# EVENTCTRL_TOP.net
KiCad netlist of a schematic drawn in Altium Designer
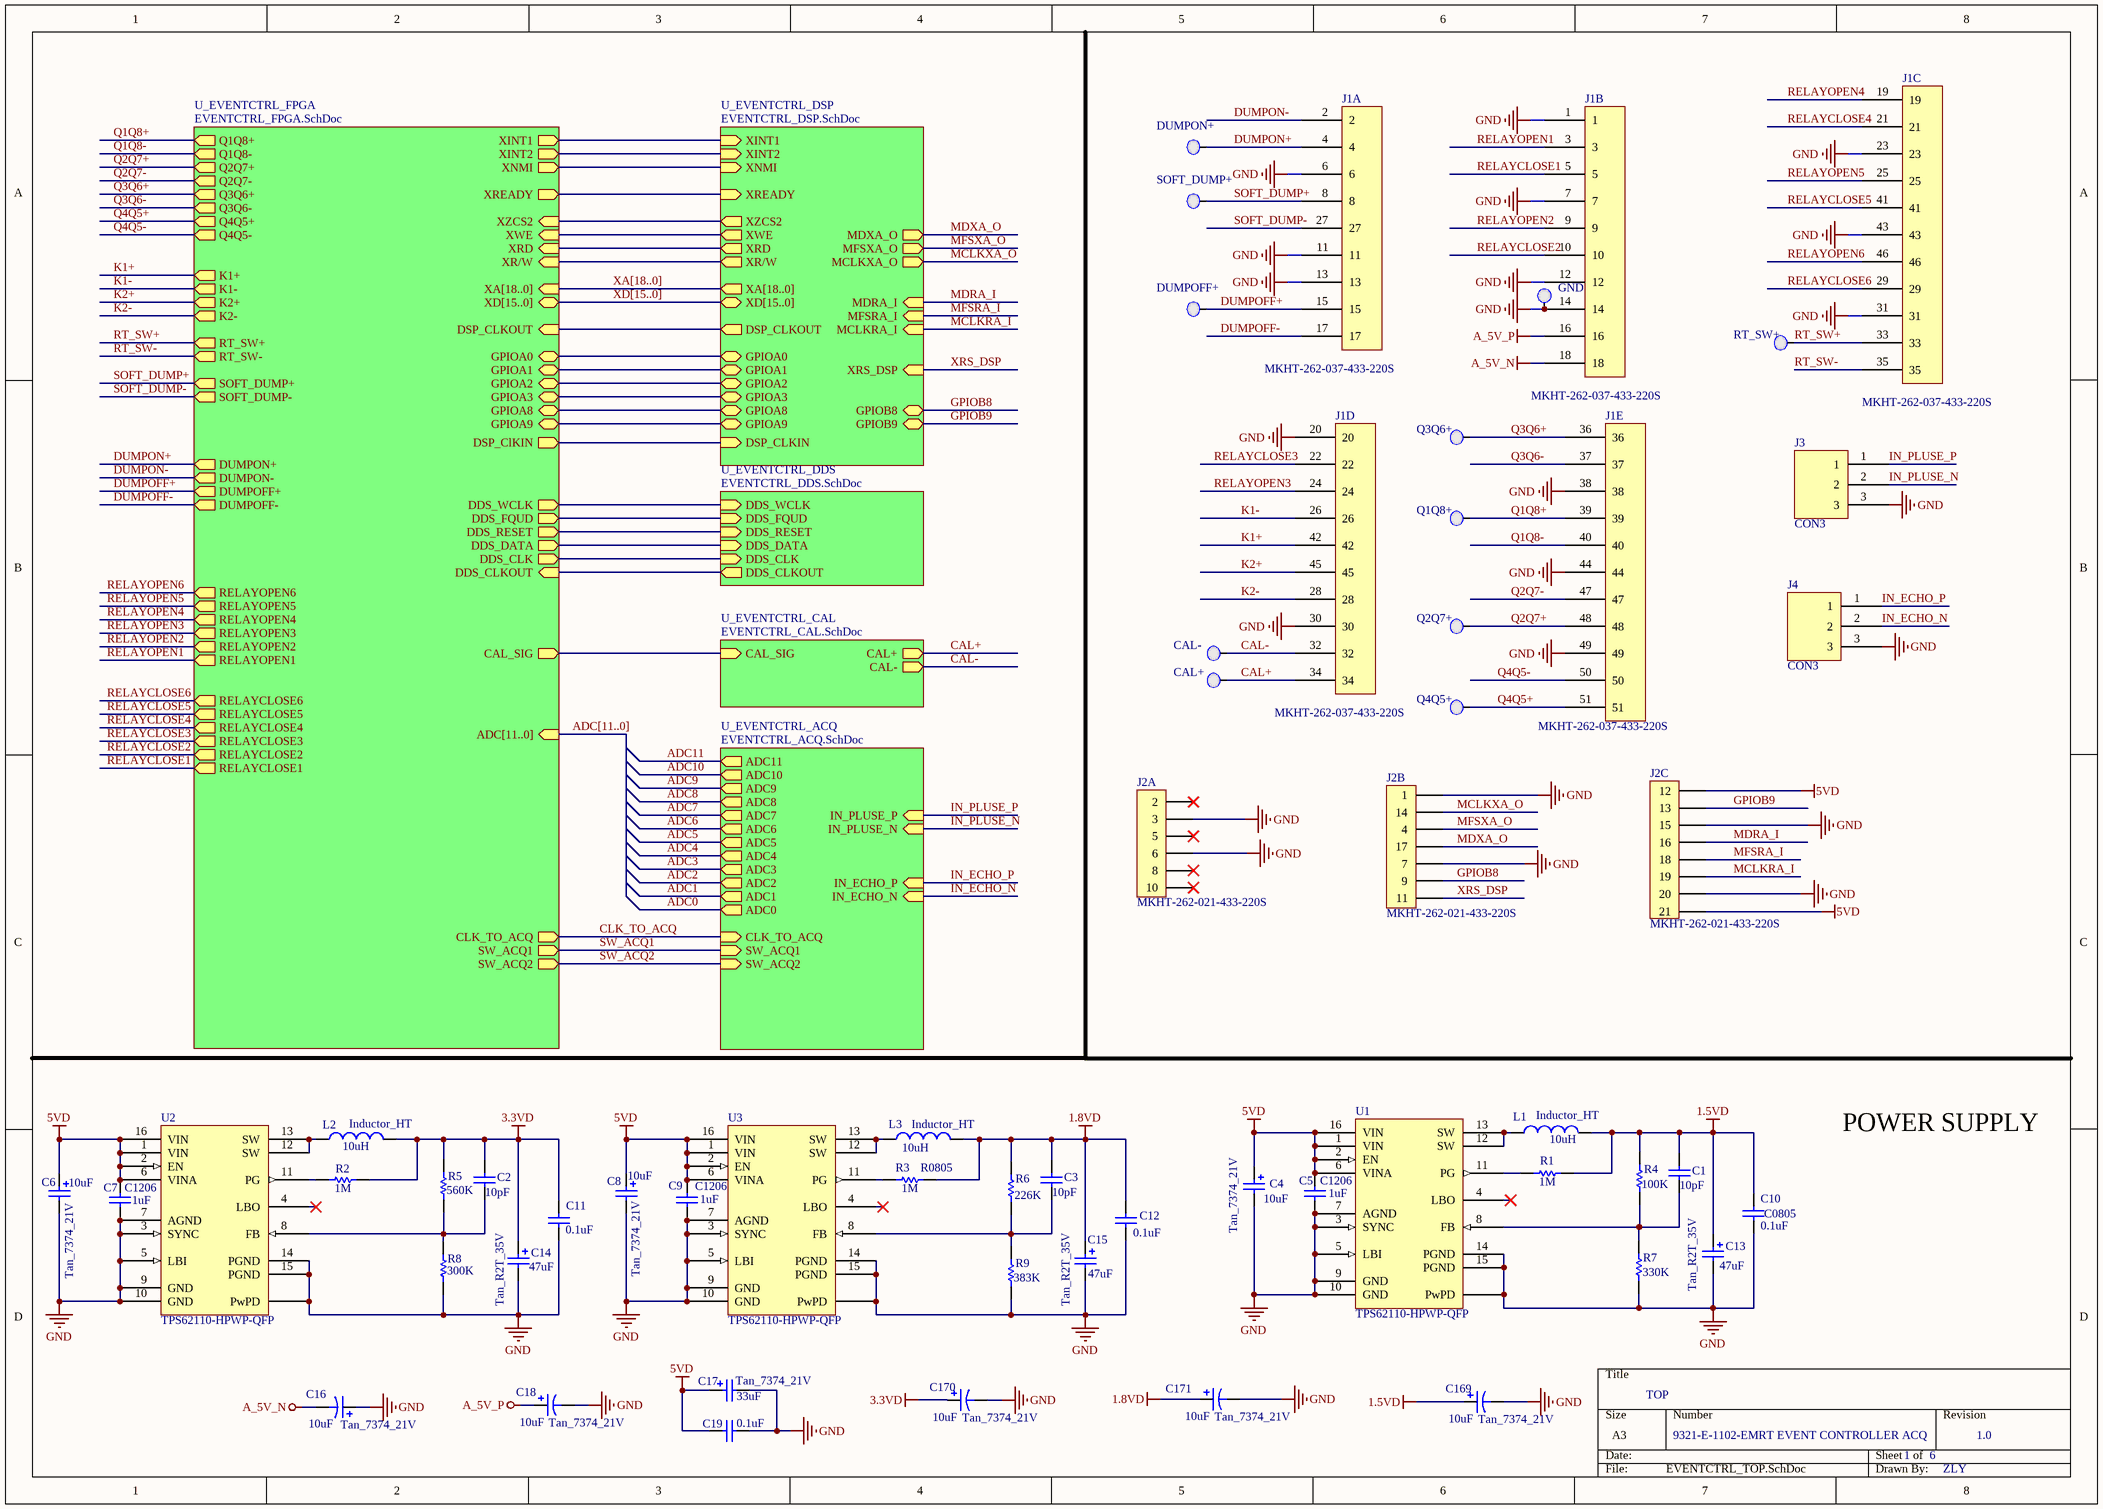
[diagram p0: EVENTCTRL_TOP.SchDoc]

(export (version "E")
  (design (tool "Eeschema 10.0.6"))
  (components
    (comp (ref "C1")
      (value "10pF")
      (footprint "0805")
      (description "Capacitor")
      (fields (field (name "PART NUMBER") "Y20025162") (field (name "Comment") "C0805"))
      (libsource (lib "Cap") (part "Cap"))
    )
    (comp (ref "C2")
      (value "10pF")
      (footprint "0805")
      (description "Capacitor")
      (fields (field (name "PART NUMBER") "Y20025162") (field (name "Comment") "C0805"))
      (libsource (lib "Cap") (part "Cap"))
    )
    (comp (ref "C3")
      (value "10pF")
      (footprint "0805")
      (description "Capacitor")
      (fields (field (name "PART NUMBER") "Y20025162") (field (name "Comment") "C0805"))
      (libsource (lib "Cap") (part "Cap"))
    )
    (comp (ref "C4")
      (value "Tan_7374_21V")
      (footprint "7343")
      (description "Polarized Capacitor")
      (fields (field (name "ALTIUM_VALUE") "10uF") (field (name "PART NUMBER") "Y20024815"))
      (libsource (lib "Cap Pol") (part "Cap Pol"))
    )
    (comp (ref "C5")
      (value "C1206")
      (footprint "1206")
      (description "Capacitor")
      (fields (field (name "ALTIUM_VALUE") "1uF") (field (name "PART NUMBER") "Y20024113"))
      (libsource (lib "Cap") (part "Cap"))
    )
    (comp (ref "C6")
      (value "Tan_7374_21V")
      (footprint "7343")
      (description "Polarized Capacitor")
      (fields (field (name "ALTIUM_VALUE") "10uF") (field (name "PART NUMBER") "Y20024815"))
      (libsource (lib "Cap Pol") (part "Cap Pol"))
    )
    (comp (ref "C7")
      (value "C1206")
      (footprint "1206")
      (description "Capacitor")
      (fields (field (name "ALTIUM_VALUE") "1uF") (field (name "PART NUMBER") "Y20024113"))
      (libsource (lib "Cap") (part "Cap"))
    )
    (comp (ref "C8")
      (value "Tan_7374_21V")
      (footprint "7343")
      (description "Polarized Capacitor")
      (fields (field (name "ALTIUM_VALUE") "10uF") (field (name "PART NUMBER") "Y20024815"))
      (libsource (lib "Cap Pol") (part "Cap Pol"))
    )
    (comp (ref "C9")
      (value "C1206")
      (footprint "1206")
      (description "Capacitor")
      (fields (field (name "ALTIUM_VALUE") "1uF") (field (name "PART NUMBER") "Y20024113"))
      (libsource (lib "Cap") (part "Cap"))
    )
    (comp (ref "C10")
      (value "C0805")
      (footprint "0805")
      (description "Capacitor")
      (fields (field (name "ALTIUM_VALUE") "0.1uF") (field (name "PART NUMBER") "Y20025084"))
      (libsource (lib "Cap") (part "Cap"))
    )
    (comp (ref "C11")
      (value "0.1uF")
      (footprint "0805")
      (description "Capacitor")
      (fields (field (name "PART NUMBER") "Y20025084") (field (name "Comment") "C0805"))
      (libsource (lib "Cap") (part "Cap"))
    )
    (comp (ref "C12")
      (value "0.1uF")
      (footprint "0805")
      (description "Capacitor")
      (fields (field (name "PART NUMBER") "Y20025084") (field (name "Comment") "C0805"))
      (libsource (lib "Cap") (part "Cap"))
    )
    (comp (ref "C13")
      (value "Tan_R2T_35V")
      (footprint "7343")
      (description "Polarized Capacitor")
      (fields (field (name "ALTIUM_VALUE") "47uF") (field (name "PART NUMBER") "Y20024816"))
      (libsource (lib "Cap Pol") (part "Cap Pol"))
    )
    (comp (ref "C14")
      (value "Tan_R2T_35V")
      (footprint "7343")
      (description "Polarized Capacitor")
      (fields (field (name "ALTIUM_VALUE") "47uF") (field (name "PART NUMBER") "Y20024816"))
      (libsource (lib "Cap Pol") (part "Cap Pol"))
    )
    (comp (ref "C15")
      (value "Tan_R2T_35V")
      (footprint "7343")
      (description "Polarized Capacitor")
      (fields (field (name "ALTIUM_VALUE") "47uF") (field (name "PART NUMBER") "Y20024816"))
      (libsource (lib "Cap Pol") (part "Cap Pol"))
    )
    (comp (ref "C16")
      (value "Tan_7374_21V")
      (footprint "7343")
      (description "Polarized Capacitor (Radial)")
      (fields (field (name "ALTIUM_VALUE") "10uF"))
      (libsource (lib "Miscellaneous Devices") (part "Cap Pol1"))
    )
    (comp (ref "C17")
      (value "Tan_7374_21V")
      (footprint "7343")
      (description "Polarized Capacitor")
      (fields (field (name "ALTIUM_VALUE") "33uF") (field (name "PART NUMBER") "Y20028884"))
      (libsource (lib "Cap Pol") (part "Cap Pol"))
    )
    (comp (ref "C18")
      (value "Tan_7374_21V")
      (footprint "7343")
      (description "Polarized Capacitor (Radial)")
      (fields (field (name "ALTIUM_VALUE") "10uF"))
      (libsource (lib "Miscellaneous Devices") (part "Cap Pol1"))
    )
    (comp (ref "C19")
      (value "0.1uF")
      (footprint "0805")
      (description "Capacitor")
      (fields (field (name "PART NUMBER") "Y20025084") (field (name "Comment") "C0805"))
      (libsource (lib "Cap") (part "Cap"))
    )
    (comp (ref "C169")
      (value "Tan_7374_21V")
      (footprint "7343")
      (description "Polarized Capacitor (Radial)")
      (fields (field (name "ALTIUM_VALUE") "10uF"))
      (libsource (lib "Miscellaneous Devices") (part "Cap Pol1"))
    )
    (comp (ref "C170")
      (value "Tan_7374_21V")
      (footprint "7343")
      (description "Polarized Capacitor (Radial)")
      (fields (field (name "ALTIUM_VALUE") "10uF"))
      (libsource (lib "Miscellaneous Devices") (part "Cap Pol1"))
    )
    (comp (ref "C171")
      (value "Tan_7374_21V")
      (footprint "7343")
      (description "Polarized Capacitor (Radial)")
      (fields (field (name "ALTIUM_VALUE") "10uF"))
      (libsource (lib "Miscellaneous Devices") (part "Cap Pol1"))
    )
    (comp (ref "CAL+") (value "TP") (footprint "TPA") (libsource (lib "*") (part "TP")))
    (comp (ref "CAL-") (value "TP") (footprint "TPA") (libsource (lib "*") (part "TP")))
    (comp (ref "DUMPOFF+") (value "TP") (footprint "TPA") (libsource (lib "*") (part "TP")))
    (comp (ref "DUMPON+") (value "TP") (footprint "TPA") (libsource (lib "*") (part "TP")))
    (comp (ref "GND") (value "TP") (footprint "TPA") (libsource (lib "") (part "TP_1")))
    (comp (ref "J1")
      (value "MKHT-262-037-433-220S")
      (footprint "MKHT-262-037-433-220S-51")
      (libsource (lib "ENEVT_SIP_MCM") (part "MKHT-262-037-433-220S"))
    )
    (comp (ref "J2")
      (value "MKHT-262-021-433-220S")
      (footprint "AIRBORN_21")
      (libsource (lib "srj") (part "MKHT-262-021-433-220S"))
    )
    (comp (ref "J3") (value "CON3") (footprint "HEAT3") (libsource (lib "srj") (part "CON3")))
    (comp (ref "J4") (value "CON3") (footprint "HEAT3") (libsource (lib "srj") (part "CON3")))
    (comp (ref "L1")
      (value "Inductor_HT")
      (footprint "Inductor_HT")
      (description "Inductor-1")
      (fields (field (name "PART NUMBER") "Y20028214") (field (name "ALTIUM_VALUE") "10uH"))
      (libsource (lib "B82422H1103K000") (part "B82422H1103K000"))
    )
    (comp (ref "L2")
      (value "Inductor_HT")
      (footprint "Inductor_HT")
      (description "Inductor-1")
      (fields (field (name "PART NUMBER") "Y20028214") (field (name "ALTIUM_VALUE") "10uH"))
      (libsource (lib "B82422H1103K000") (part "B82422H1103K000"))
    )
    (comp (ref "L3")
      (value "Inductor_HT")
      (footprint "Inductor_HT")
      (description "Inductor-1")
      (fields (field (name "PART NUMBER") "Y20028214") (field (name "ALTIUM_VALUE") "10uH"))
      (libsource (lib "B82422H1103K000") (part "B82422H1103K000"))
    )
    (comp (ref "Q1Q8+") (value "TP") (footprint "TPA") (libsource (lib "*") (part "TP")))
    (comp (ref "Q2Q7+") (value "TP") (footprint "TPA") (libsource (lib "*") (part "TP")))
    (comp (ref "Q3Q6+") (value "TP") (footprint "TPA") (libsource (lib "*") (part "TP")))
    (comp (ref "Q4Q5+") (value "TP") (footprint "TPA") (libsource (lib "*") (part "TP")))
    (comp (ref "R1")
      (value "1M")
      (footprint "R0805")
      (description "Resistor")
      (fields (field (name "Comment") "R0805") (field (name "PUBLISHER") "Altium Limited"))
      (libsource (lib "Miscellaneous Devices") (part "Res1"))
    )
    (comp (ref "R2")
      (value "1M")
      (footprint "R0805")
      (description "Resistor")
      (fields (field (name "Comment") "R0805") (field (name "PUBLISHER") "Altium Limited"))
      (libsource (lib "Miscellaneous Devices") (part "Res1"))
    )
    (comp (ref "R3")
      (value "R0805")
      (footprint "R0805")
      (description "Resistor")
      (fields (field (name "ALTIUM_VALUE") "1M") (field (name "PUBLISHER") "Altium Limited"))
      (libsource (lib "Miscellaneous Devices") (part "Res1"))
    )
    (comp (ref "R4")
      (value "100K")
      (footprint "R0805")
      (description "Resistor")
      (fields (field (name "Comment") "R0805") (field (name "PUBLISHER") "Altium Limited"))
      (libsource (lib "Miscellaneous Devices") (part "Res1"))
    )
    (comp (ref "R5")
      (value "560K")
      (footprint "R0805")
      (description "Resistor")
      (fields (field (name "Comment") "R0805") (field (name "PUBLISHER") "Altium Limited"))
      (libsource (lib "Miscellaneous Devices") (part "Res1"))
    )
    (comp (ref "R6")
      (value "226K")
      (footprint "R0805")
      (description "Resistor")
      (fields (field (name "Comment") "R0805") (field (name "PUBLISHER") "Altium Limited"))
      (libsource (lib "Miscellaneous Devices") (part "Res1"))
    )
    (comp (ref "R7")
      (value "330K")
      (footprint "R0805")
      (description "Resistor")
      (fields (field (name "Comment") "R0805") (field (name "PUBLISHER") "Altium Limited"))
      (libsource (lib "Miscellaneous Devices") (part "Res1"))
    )
    (comp (ref "R8")
      (value "300K")
      (footprint "R0805")
      (description "Resistor")
      (fields (field (name "Comment") "R0805") (field (name "PUBLISHER") "Altium Limited"))
      (libsource (lib "Miscellaneous Devices") (part "Res1"))
    )
    (comp (ref "R9")
      (value "383K")
      (footprint "R0805")
      (description "Resistor")
      (fields (field (name "Comment") "R0805") (field (name "PUBLISHER") "Altium Limited"))
      (libsource (lib "Miscellaneous Devices") (part "Res1"))
    )
    (comp (ref "RT_SW+") (value "TP") (footprint "TPA") (libsource (lib "*") (part "TP")))
    (comp (ref "SOFT_DUMP+") (value "TP") (footprint "TPA") (libsource (lib "*") (part "TP")))
    (comp (ref "U1")
      (value "TPS62110-HPWP-QFP")
      (footprint "PWP16")
      (fields (field (name "PART NUMBER") "Y20033002"))
      (libsource (lib "TPS62110-HT") (part "TPS62110-HPWP"))
    )
    (comp (ref "U2")
      (value "TPS62110-HPWP-QFP")
      (footprint "PWP16")
      (fields (field (name "PART NUMBER") "Y20033002"))
      (libsource (lib "TPS62110-HT") (part "TPS62110-HPWP"))
    )
    (comp (ref "U3")
      (value "TPS62110-HPWP-QFP")
      (footprint "PWP16")
      (fields (field (name "PART NUMBER") "Y20033002"))
      (libsource (lib "TPS62110-HT") (part "TPS62110-HPWP"))
    )
  )
  (nets
    (net (code "49") (name "/CAL+") (class "Default")
      (node (ref "CAL+") (pin "1") (pinfunction "TP_1") (pintype "passive"))
      (node (ref "J1") (pin "34") (pinfunction "34_34") (pintype "passive"))
    )
    (net (code "50") (name "/CAL-") (class "Default")
      (node (ref "CAL-") (pin "1") (pinfunction "TP_1") (pintype "passive"))
      (node (ref "J1") (pin "32") (pinfunction "32_32") (pintype "passive"))
    )
    (net (code "61") (name "/DUMPOFF+") (class "Default")
      (node (ref "DUMPOFF+") (pin "1") (pinfunction "TP_1") (pintype "passive"))
      (node (ref "J1") (pin "15") (pinfunction "15_15") (pintype "passive"))
    )
    (net (code "62") (name "/DUMPOFF-") (class "Default")
      (node (ref "J1") (pin "17") (pinfunction "17_17") (pintype "passive"))
    )
    (net (code "63") (name "/DUMPON+") (class "Default")
      (node (ref "DUMPON+") (pin "1") (pinfunction "TP_1") (pintype "passive"))
      (node (ref "J1") (pin "4") (pinfunction "4_4") (pintype "passive"))
    )
    (net (code "64") (name "/DUMPON-") (class "Default")
      (node (ref "J1") (pin "2") (pinfunction "2_2") (pintype "passive"))
    )
    (net (code "71") (name "/GPIOB8") (class "Default")
      (node (ref "J2") (pin "9") (pinfunction "9_9") (pintype "passive"))
    )
    (net (code "72") (name "/GPIOB9") (class "Default")
      (node (ref "J2") (pin "13") (pinfunction "13_13") (pintype "passive"))
    )
    (net (code "73") (name "/IN_ECHO_N") (class "Default")
      (node (ref "J4") (pin "2") (pinfunction "2_2") (pintype "passive"))
    )
    (net (code "74") (name "/IN_ECHO_P") (class "Default")
      (node (ref "J4") (pin "1") (pinfunction "1_1") (pintype "passive"))
    )
    (net (code "75") (name "/IN_PLUSE_N") (class "Default")
      (node (ref "J3") (pin "2") (pinfunction "2_2") (pintype "passive"))
    )
    (net (code "76") (name "/IN_PLUSE_P") (class "Default")
      (node (ref "J3") (pin "1") (pinfunction "1_1") (pintype "passive"))
    )
    (net (code "77") (name "/K1+") (class "Default")
      (node (ref "J1") (pin "42") (pinfunction "42_42") (pintype "passive"))
    )
    (net (code "78") (name "/K1-") (class "Default")
      (node (ref "J1") (pin "26") (pinfunction "26_26") (pintype "passive"))
    )
    (net (code "79") (name "/K2+") (class "Default")
      (node (ref "J1") (pin "45") (pinfunction "45_45") (pintype "passive"))
    )
    (net (code "80") (name "/K2-") (class "Default")
      (node (ref "J1") (pin "28") (pinfunction "28_28") (pintype "passive"))
    )
    (net (code "81") (name "/MCLKRA_I") (class "Default")
      (node (ref "J2") (pin "19") (pinfunction "19_19") (pintype "passive"))
    )
    (net (code "82") (name "/MCLKXA_O") (class "Default")
      (node (ref "J2") (pin "14") (pinfunction "14_14") (pintype "passive"))
    )
    (net (code "83") (name "/MDRA_I") (class "Default")
      (node (ref "J2") (pin "16") (pinfunction "16_16") (pintype "passive"))
    )
    (net (code "84") (name "/MDXA_O") (class "Default")
      (node (ref "J2") (pin "17") (pinfunction "17_17") (pintype "passive"))
    )
    (net (code "85") (name "/MFSRA_I") (class "Default")
      (node (ref "J2") (pin "18") (pinfunction "18_18") (pintype "passive"))
    )
    (net (code "86") (name "/MFSXA_O") (class "Default")
      (node (ref "J2") (pin "4") (pinfunction "4_4") (pintype "passive"))
    )
    (net (code "87") (name "/Q1Q8+") (class "Default")
      (node (ref "J1") (pin "39") (pinfunction "39_39") (pintype "passive"))
      (node (ref "Q1Q8+") (pin "1") (pinfunction "TP_1") (pintype "passive"))
    )
    (net (code "88") (name "/Q1Q8-") (class "Default")
      (node (ref "J1") (pin "40") (pinfunction "40_40") (pintype "passive"))
    )
    (net (code "89") (name "/Q2Q7+") (class "Default")
      (node (ref "J1") (pin "48") (pinfunction "48_48") (pintype "passive"))
      (node (ref "Q2Q7+") (pin "1") (pinfunction "TP_1") (pintype "passive"))
    )
    (net (code "90") (name "/Q2Q7-") (class "Default")
      (node (ref "J1") (pin "47") (pinfunction "47_47") (pintype "passive"))
    )
    (net (code "91") (name "/Q3Q6+") (class "Default")
      (node (ref "J1") (pin "36") (pinfunction "36_36") (pintype "passive"))
      (node (ref "Q3Q6+") (pin "1") (pinfunction "TP_1") (pintype "passive"))
    )
    (net (code "92") (name "/Q3Q6-") (class "Default")
      (node (ref "J1") (pin "37") (pinfunction "37_37") (pintype "passive"))
    )
    (net (code "93") (name "/Q4Q5+") (class "Default")
      (node (ref "J1") (pin "51") (pinfunction "51_51") (pintype "passive"))
      (node (ref "Q4Q5+") (pin "1") (pinfunction "TP_1") (pintype "passive"))
    )
    (net (code "94") (name "/Q4Q5-") (class "Default")
      (node (ref "J1") (pin "50") (pinfunction "50_50") (pintype "passive"))
    )
    (net (code "95") (name "/RELAYCLOSE1") (class "Default")
      (node (ref "J1") (pin "5") (pinfunction "5_5") (pintype "passive"))
    )
    (net (code "96") (name "/RELAYCLOSE2") (class "Default")
      (node (ref "J1") (pin "10") (pinfunction "10_10") (pintype "passive"))
    )
    (net (code "97") (name "/RELAYCLOSE3") (class "Default")
      (node (ref "J1") (pin "22") (pinfunction "22_22") (pintype "passive"))
    )
    (net (code "98") (name "/RELAYCLOSE4") (class "Default")
      (node (ref "J1") (pin "21") (pinfunction "21_21") (pintype "passive"))
    )
    (net (code "99") (name "/RELAYCLOSE5") (class "Default")
      (node (ref "J1") (pin "41") (pinfunction "41_41") (pintype "passive"))
    )
    (net (code "100") (name "/RELAYCLOSE6") (class "Default")
      (node (ref "J1") (pin "29") (pinfunction "29_29") (pintype "passive"))
    )
    (net (code "101") (name "/RELAYOPEN1") (class "Default")
      (node (ref "J1") (pin "3") (pinfunction "3_3") (pintype "passive"))
    )
    (net (code "102") (name "/RELAYOPEN2") (class "Default")
      (node (ref "J1") (pin "9") (pinfunction "9_9") (pintype "passive"))
    )
    (net (code "103") (name "/RELAYOPEN3") (class "Default")
      (node (ref "J1") (pin "24") (pinfunction "24_24") (pintype "passive"))
    )
    (net (code "104") (name "/RELAYOPEN4") (class "Default")
      (node (ref "J1") (pin "19") (pinfunction "19_19") (pintype "passive"))
    )
    (net (code "105") (name "/RELAYOPEN5") (class "Default")
      (node (ref "J1") (pin "25") (pinfunction "25_25") (pintype "passive"))
    )
    (net (code "106") (name "/RELAYOPEN6") (class "Default")
      (node (ref "J1") (pin "46") (pinfunction "46_46") (pintype "passive"))
    )
    (net (code "107") (name "/RT_SW+") (class "Default")
      (node (ref "J1") (pin "33") (pinfunction "33_33") (pintype "passive"))
      (node (ref "RT_SW+") (pin "1") (pinfunction "TP_1") (pintype "passive"))
    )
    (net (code "108") (name "/RT_SW-") (class "Default")
      (node (ref "J1") (pin "35") (pinfunction "35_35") (pintype "passive"))
    )
    (net (code "109") (name "/SOFT_DUMP+") (class "Default")
      (node (ref "J1") (pin "8") (pinfunction "8_8") (pintype "passive"))
      (node (ref "SOFT_DUMP+") (pin "1") (pinfunction "TP_1") (pintype "passive"))
    )
    (net (code "110") (name "/SOFT_DUMP-") (class "Default")
      (node (ref "J1") (pin "27") (pinfunction "27_27") (pintype "passive"))
    )
    (net (code "120") (name "/XRS_DSP") (class "Default")
      (node (ref "J2") (pin "11") (pinfunction "11_11") (pintype "passive"))
    )
    (net (code "124") (name "1.5VD") (class "Default")
      (node (ref "C1") (pin "2") (pinfunction "2_2") (pintype "passive"))
      (node (ref "C10") (pin "2") (pinfunction "2_2") (pintype "passive"))
      (node (ref "C13") (pin "1") (pinfunction "1_1") (pintype "passive"))
      (node (ref "C169") (pin "1") (pinfunction "1_1") (pintype "passive"))
      (node (ref "L1") (pin "2") (pinfunction "2_2") (pintype "passive"))
      (node (ref "R1") (pin "2") (pinfunction "2_2") (pintype "passive"))
      (node (ref "R4") (pin "2") (pinfunction "2_2") (pintype "passive"))
    )
    (net (code "125") (name "1.8VD") (class "Default")
      (node (ref "C12") (pin "2") (pinfunction "2_2") (pintype "passive"))
      (node (ref "C15") (pin "1") (pinfunction "1_1") (pintype "passive"))
      (node (ref "C171") (pin "1") (pinfunction "1_1") (pintype "passive"))
      (node (ref "C3") (pin "2") (pinfunction "2_2") (pintype "passive"))
      (node (ref "L3") (pin "2") (pinfunction "2_2") (pintype "passive"))
      (node (ref "R3") (pin "2") (pinfunction "2_2") (pintype "passive"))
      (node (ref "R6") (pin "2") (pinfunction "2_2") (pintype "passive"))
    )
    (net (code "126") (name "3.3VD") (class "Default")
      (node (ref "C11") (pin "2") (pinfunction "2_2") (pintype "passive"))
      (node (ref "C14") (pin "1") (pinfunction "1_1") (pintype "passive"))
      (node (ref "C170") (pin "1") (pinfunction "1_1") (pintype "passive"))
      (node (ref "C2") (pin "2") (pinfunction "2_2") (pintype "passive"))
      (node (ref "L2") (pin "2") (pinfunction "2_2") (pintype "passive"))
      (node (ref "R2") (pin "2") (pinfunction "2_2") (pintype "passive"))
      (node (ref "R5") (pin "2") (pinfunction "2_2") (pintype "passive"))
    )
    (net (code "127") (name "5VD") (class "Default")
      (node (ref "C17") (pin "1") (pinfunction "1_1") (pintype "passive"))
      (node (ref "C19") (pin "2") (pinfunction "2_2") (pintype "passive"))
      (node (ref "C4") (pin "1") (pinfunction "1_1") (pintype "passive"))
      (node (ref "C5") (pin "2") (pinfunction "2_2") (pintype "passive"))
      (node (ref "C6") (pin "1") (pinfunction "1_1") (pintype "passive"))
      (node (ref "C7") (pin "2") (pinfunction "2_2") (pintype "passive"))
      (node (ref "C8") (pin "1") (pinfunction "1_1") (pintype "passive"))
      (node (ref "C9") (pin "2") (pinfunction "2_2") (pintype "passive"))
      (node (ref "J2") (pin "12") (pinfunction "12_12") (pintype "passive"))
      (node (ref "J2") (pin "21") (pinfunction "21_21") (pintype "power_in"))
      (node (ref "U1") (pin "1") (pinfunction "VIN_1") (pintype "power_in"))
      (node (ref "U1") (pin "16") (pinfunction "VIN_16") (pintype "power_in"))
      (node (ref "U1") (pin "2") (pinfunction "EN_2") (pintype "input"))
      (node (ref "U1") (pin "6") (pinfunction "VINA_6") (pintype "power_in"))
      (node (ref "U2") (pin "1") (pinfunction "VIN_1") (pintype "power_in"))
      (node (ref "U2") (pin "16") (pinfunction "VIN_16") (pintype "power_in"))
      (node (ref "U2") (pin "2") (pinfunction "EN_2") (pintype "input"))
      (node (ref "U2") (pin "6") (pinfunction "VINA_6") (pintype "power_in"))
      (node (ref "U3") (pin "1") (pinfunction "VIN_1") (pintype "power_in"))
      (node (ref "U3") (pin "16") (pinfunction "VIN_16") (pintype "power_in"))
      (node (ref "U3") (pin "2") (pinfunction "EN_2") (pintype "input"))
      (node (ref "U3") (pin "6") (pinfunction "VINA_6") (pintype "power_in"))
    )
    (net (code "128") (name "A_5V_N") (class "Default")
      (node (ref "C16") (pin "2") (pinfunction "2_2") (pintype "passive"))
      (node (ref "J1") (pin "18") (pinfunction "18_18") (pintype "passive"))
    )
    (net (code "129") (name "A_5V_P") (class "Default")
      (node (ref "C18") (pin "1") (pinfunction "1_1") (pintype "passive"))
      (node (ref "J1") (pin "16") (pinfunction "16_16") (pintype "passive"))
    )
    (net (code "130") (name "GND") (class "Default")
      (node (ref "C10") (pin "1") (pinfunction "1_1") (pintype "passive"))
      (node (ref "C11") (pin "1") (pinfunction "1_1") (pintype "passive"))
      (node (ref "C12") (pin "1") (pinfunction "1_1") (pintype "passive"))
      (node (ref "C13") (pin "2") (pinfunction "2_2") (pintype "passive"))
      (node (ref "C14") (pin "2") (pinfunction "2_2") (pintype "passive"))
      (node (ref "C15") (pin "2") (pinfunction "2_2") (pintype "passive"))
      (node (ref "C16") (pin "1") (pinfunction "1_1") (pintype "passive"))
      (node (ref "C169") (pin "2") (pinfunction "2_2") (pintype "passive"))
      (node (ref "C17") (pin "2") (pinfunction "2_2") (pintype "passive"))
      (node (ref "C170") (pin "2") (pinfunction "2_2") (pintype "passive"))
      (node (ref "C171") (pin "2") (pinfunction "2_2") (pintype "passive"))
      (node (ref "C18") (pin "2") (pinfunction "2_2") (pintype "passive"))
      (node (ref "C19") (pin "1") (pinfunction "1_1") (pintype "passive"))
      (node (ref "C4") (pin "2") (pinfunction "2_2") (pintype "passive"))
      (node (ref "C5") (pin "1") (pinfunction "1_1") (pintype "passive"))
      (node (ref "C6") (pin "2") (pinfunction "2_2") (pintype "passive"))
      (node (ref "C7") (pin "1") (pinfunction "1_1") (pintype "passive"))
      (node (ref "C8") (pin "2") (pinfunction "2_2") (pintype "passive"))
      (node (ref "C9") (pin "1") (pinfunction "1_1") (pintype "passive"))
      (node (ref "GND") (pin "1") (pinfunction "TP_1") (pintype "passive"))
      (node (ref "J1") (pin "1") (pinfunction "1_1") (pintype "passive"))
      (node (ref "J1") (pin "11") (pinfunction "11_11") (pintype "passive"))
      (node (ref "J1") (pin "12") (pinfunction "12_12") (pintype "passive"))
      (node (ref "J1") (pin "13") (pinfunction "13_13") (pintype "passive"))
      (node (ref "J1") (pin "14") (pinfunction "14_14") (pintype "passive"))
      (node (ref "J1") (pin "20") (pinfunction "20_20") (pintype "passive"))
      (node (ref "J1") (pin "23") (pinfunction "23_23") (pintype "passive"))
      (node (ref "J1") (pin "30") (pinfunction "30_30") (pintype "passive"))
      (node (ref "J1") (pin "31") (pinfunction "31_31") (pintype "passive"))
      (node (ref "J1") (pin "38") (pinfunction "38_38") (pintype "passive"))
      (node (ref "J1") (pin "43") (pinfunction "43_43") (pintype "passive"))
      (node (ref "J1") (pin "44") (pinfunction "44_44") (pintype "passive"))
      (node (ref "J1") (pin "49") (pinfunction "49_49") (pintype "passive"))
      (node (ref "J1") (pin "6") (pinfunction "6_6") (pintype "passive"))
      (node (ref "J1") (pin "7") (pinfunction "7_7") (pintype "passive"))
      (node (ref "J2") (pin "1") (pinfunction "1_1") (pintype "passive"))
      (node (ref "J2") (pin "15") (pinfunction "15_15") (pintype "passive"))
      (node (ref "J2") (pin "20") (pinfunction "20_20") (pintype "passive"))
      (node (ref "J2") (pin "3") (pinfunction "3_3") (pintype "passive"))
      (node (ref "J2") (pin "6") (pinfunction "6_6") (pintype "passive"))
      (node (ref "J2") (pin "7") (pinfunction "7_7") (pintype "passive"))
      (node (ref "J3") (pin "3") (pinfunction "3_3") (pintype "passive"))
      (node (ref "J4") (pin "3") (pinfunction "3_3") (pintype "passive"))
      (node (ref "R7") (pin "1") (pinfunction "1_1") (pintype "passive"))
      (node (ref "R8") (pin "1") (pinfunction "1_1") (pintype "passive"))
      (node (ref "R9") (pin "1") (pinfunction "1_1") (pintype "passive"))
      (node (ref "U1") (pin "10") (pinfunction "GND_10") (pintype "passive"))
      (node (ref "U1") (pin "14") (pinfunction "PGND_14") (pintype "passive"))
      (node (ref "U1") (pin "15") (pinfunction "PGND_15") (pintype "passive"))
      (node (ref "U1") (pin "3") (pinfunction "SYNC_3") (pintype "input"))
      (node (ref "U1") (pin "5") (pinfunction "LBI_5") (pintype "input"))
      (node (ref "U1") (pin "7") (pinfunction "AGND_7") (pintype "power_in"))
      (node (ref "U1") (pin "9") (pinfunction "GND_9") (pintype "passive"))
      (node (ref "U1") (pin "PwPD") (pinfunction "PwPD_PwPD") (pintype "passive"))
      (node (ref "U2") (pin "10") (pinfunction "GND_10") (pintype "passive"))
      (node (ref "U2") (pin "14") (pinfunction "PGND_14") (pintype "passive"))
      (node (ref "U2") (pin "15") (pinfunction "PGND_15") (pintype "passive"))
      (node (ref "U2") (pin "3") (pinfunction "SYNC_3") (pintype "input"))
      (node (ref "U2") (pin "5") (pinfunction "LBI_5") (pintype "input"))
      (node (ref "U2") (pin "7") (pinfunction "AGND_7") (pintype "power_in"))
      (node (ref "U2") (pin "9") (pinfunction "GND_9") (pintype "passive"))
      (node (ref "U2") (pin "PwPD") (pinfunction "PwPD_PwPD") (pintype "passive"))
      (node (ref "U3") (pin "10") (pinfunction "GND_10") (pintype "passive"))
      (node (ref "U3") (pin "14") (pinfunction "PGND_14") (pintype "passive"))
      (node (ref "U3") (pin "15") (pinfunction "PGND_15") (pintype "passive"))
      (node (ref "U3") (pin "3") (pinfunction "SYNC_3") (pintype "input"))
      (node (ref "U3") (pin "5") (pinfunction "LBI_5") (pintype "input"))
      (node (ref "U3") (pin "7") (pinfunction "AGND_7") (pintype "power_in"))
      (node (ref "U3") (pin "9") (pinfunction "GND_9") (pintype "passive"))
      (node (ref "U3") (pin "PwPD") (pinfunction "PwPD_PwPD") (pintype "passive"))
    )
    (net (code "131") (name "Net-(L1-Pad1)") (class "Default")
      (node (ref "L1") (pin "1") (pinfunction "1_1") (pintype "passive"))
      (node (ref "U1") (pin "12") (pinfunction "SW_12") (pintype "passive"))
      (node (ref "U1") (pin "13") (pinfunction "SW_13") (pintype "passive"))
    )
    (net (code "132") (name "Net-(L2-Pad1)") (class "Default")
      (node (ref "L2") (pin "1") (pinfunction "1_1") (pintype "passive"))
      (node (ref "U2") (pin "12") (pinfunction "SW_12") (pintype "passive"))
      (node (ref "U2") (pin "13") (pinfunction "SW_13") (pintype "passive"))
    )
    (net (code "133") (name "Net-(L3-Pad1)") (class "Default")
      (node (ref "L3") (pin "1") (pinfunction "1_1") (pintype "passive"))
      (node (ref "U3") (pin "12") (pinfunction "SW_12") (pintype "passive"))
      (node (ref "U3") (pin "13") (pinfunction "SW_13") (pintype "passive"))
    )
    (net (code "134") (name "Net-(U1-FB)") (class "Default")
      (node (ref "C1") (pin "1") (pinfunction "1_1") (pintype "passive"))
      (node (ref "R4") (pin "1") (pinfunction "1_1") (pintype "passive"))
      (node (ref "R7") (pin "2") (pinfunction "2_2") (pintype "passive"))
      (node (ref "U1") (pin "8") (pinfunction "FB_8") (pintype "input"))
    )
    (net (code "135") (name "Net-(U1-PG)") (class "Default")
      (node (ref "R1") (pin "1") (pinfunction "1_1") (pintype "passive"))
      (node (ref "U1") (pin "11") (pinfunction "PG_11") (pintype "output"))
    )
    (net (code "136") (name "Net-(U2-FB)") (class "Default")
      (node (ref "C2") (pin "1") (pinfunction "1_1") (pintype "passive"))
      (node (ref "R5") (pin "1") (pinfunction "1_1") (pintype "passive"))
      (node (ref "R8") (pin "2") (pinfunction "2_2") (pintype "passive"))
      (node (ref "U2") (pin "8") (pinfunction "FB_8") (pintype "input"))
    )
    (net (code "137") (name "Net-(U2-PG)") (class "Default")
      (node (ref "R2") (pin "1") (pinfunction "1_1") (pintype "passive"))
      (node (ref "U2") (pin "11") (pinfunction "PG_11") (pintype "output"))
    )
    (net (code "138") (name "Net-(U3-FB)") (class "Default")
      (node (ref "C3") (pin "1") (pinfunction "1_1") (pintype "passive"))
      (node (ref "R6") (pin "1") (pinfunction "1_1") (pintype "passive"))
      (node (ref "R9") (pin "2") (pinfunction "2_2") (pintype "passive"))
      (node (ref "U3") (pin "8") (pinfunction "FB_8") (pintype "input"))
    )
    (net (code "139") (name "Net-(U3-PG)") (class "Default")
      (node (ref "R3") (pin "1") (pinfunction "1_1") (pintype "passive"))
      (node (ref "U3") (pin "11") (pinfunction "PG_11") (pintype "output"))
    )
    (net (code "140") (name "unconnected-(J2-Pad2)") (class "Default")
      (node (ref "J2") (pin "2") (pinfunction "2_2") (pintype "passive+no_connect"))
    )
    (net (code "141") (name "unconnected-(J2-Pad5)") (class "Default")
      (node (ref "J2") (pin "5") (pinfunction "5_5") (pintype "passive+no_connect"))
    )
    (net (code "142") (name "unconnected-(J2-Pad8)") (class "Default")
      (node (ref "J2") (pin "8") (pinfunction "8_8") (pintype "passive+no_connect"))
    )
    (net (code "143") (name "unconnected-(J2-Pad10)") (class "Default")
      (node (ref "J2") (pin "10") (pinfunction "10_10") (pintype "passive+no_connect"))
    )
    (net (code "144") (name "unconnected-(U1-LBO-Pad4)") (class "Default")
      (node (ref "U1") (pin "4") (pinfunction "LBO_4") (pintype "passive+no_connect"))
    )
    (net (code "145") (name "unconnected-(U2-LBO-Pad4)") (class "Default")
      (node (ref "U2") (pin "4") (pinfunction "LBO_4") (pintype "passive+no_connect"))
    )
    (net (code "146") (name "unconnected-(U3-LBO-Pad4)") (class "Default")
      (node (ref "U3") (pin "4") (pinfunction "LBO_4") (pintype "passive+no_connect"))
    )
  )
)
